# GPS.net
KiCad netlist of a schematic drawn in Altium Designer
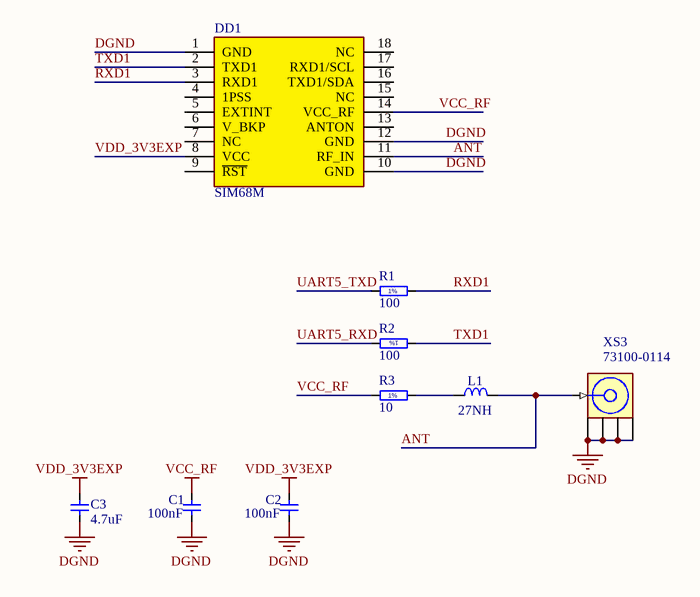
[diagram p0: GPS.SchDoc]

(export (version "E")
  (design (tool "Eeschema 10.0.6"))
  (components
    (comp (ref "C1")
      (value "100nF")
      (footprint "CAP0603R")
      (description "SMD 0805 Capacitor")
      (fields
        (field (name "PART NUMBER") "CC0603_100NF_50V_10%_X7R")
        (field (name "VOLTAGE") "50V")
        (field (name "AUTHOR") "I. Kuznetsov")
      )
      (libsource (lib "Capacitor") (part "CAP_NON_POLAR"))
    )
    (comp (ref "C2")
      (value "100nF")
      (footprint "CAP0603R")
      (description "SMD 0805 Capacitor")
      (fields
        (field (name "PART NUMBER") "CC0603_100NF_50V_10%_X7R")
        (field (name "VOLTAGE") "50V")
        (field (name "AUTHOR") "I. Kuznetsov")
      )
      (libsource (lib "Capacitor") (part "CAP_NON_POLAR"))
    )
    (comp (ref "C3")
      (value "4.7uF")
      (footprint "CAP0603R")
      (description "SMD 0805 Capacitor")
      (fields
        (field (name "PART NUMBER") "CC0603_4.7UF_6.3V_10%_X5R")
        (field (name "VOLTAGE") "6.3V")
        (field (name "AUTHOR") "I. Kuznetsov")
      )
      (libsource (lib "Capacitor") (part "CAP_NON_POLAR"))
    )
    (comp (ref "DD1")
      (value "SIM68M")
      (footprint "SIM68M")
      (fields (field (name "AUTHOR") "I. Kuznetsov"))
      (libsource (lib "IC And Semiconductor") (part "SIM68M"))
    )
    (comp (ref "L1")
      (value "27NH")
      (footprint "INDC1608X75N")
      (description "Inductor")
      (fields
        (field (name "PART NUMBER") "IND0603_TDK_MMZ1608B601C")
        (field (name "POWER") "500mA")
        (field (name "AUTHOR") "CERN DEM JMW")
      )
      (libsource (lib "Inductors & Transformers") (part "Inductor"))
    )
    (comp (ref "R1")
      (value "100")
      (footprint "RES0603R")
      (fields
        (field (name "PART NUMBER") "R0603_100R_1%_0.1W_100PPM")
        (field (name "POWER") "0.1W")
        (field (name "TOLERANCE") "±1%")
        (field (name "AUTHOR") "CERN DEM JLC")
      )
      (libsource (lib "Resistor") (part "Resistor - 1%"))
    )
    (comp (ref "R2")
      (value "100")
      (footprint "RES0603R")
      (fields
        (field (name "PART NUMBER") "R0603_100R_1%_0.1W_100PPM")
        (field (name "POWER") "0.1W")
        (field (name "TOLERANCE") "±1%")
        (field (name "AUTHOR") "CERN DEM JLC")
      )
      (libsource (lib "Resistor") (part "Resistor - 1%"))
    )
    (comp (ref "R3")
      (value "10")
      (footprint "RES0603R")
      (fields
        (field (name "PART NUMBER") "R0603_10R_1%_0.1W_200PPM")
        (field (name "POWER") "0.1W")
        (field (name "TOLERANCE") "±1%")
        (field (name "AUTHOR") "CERN DEM JLC")
      )
      (libsource (lib "Resistor") (part "Resistor - 1%"))
    )
    (comp (ref "XS3")
      (value "73100-0114")
      (footprint "73100-0114")
      (fields (field (name "MANUFACTURER") "MOLEX"))
      (libsource (lib "Connector") (part "COAX-F"))
    )
  )
  (nets
    (net (code "1") (name "/ANT") (class "Default")
      (node (ref "DD1") (pin "11") (pinfunction "RF_IN_11") (pintype "passive"))
      (node (ref "L1") (pin "2") (pinfunction "2_2") (pintype "passive"))
      (node (ref "XS3") (pin "1") (pinfunction "Signal_1") (pintype "input"))
    )
    (net (code "2") (name "/RXD1") (class "Default")
      (node (ref "DD1") (pin "3") (pinfunction "RXD1_3") (pintype "passive"))
      (node (ref "R1") (pin "2") (pinfunction "2_2") (pintype "passive"))
    )
    (net (code "3") (name "/TXD1") (class "Default")
      (node (ref "DD1") (pin "2") (pinfunction "TXD1_2") (pintype "passive"))
      (node (ref "R2") (pin "1") (pinfunction "1_1") (pintype "passive"))
    )
    (net (code "4") (name "/UART5_RXD") (class "Default")
      (node (ref "R2") (pin "2") (pinfunction "2_2") (pintype "passive"))
    )
    (net (code "5") (name "/UART5_TXD") (class "Default")
      (node (ref "R1") (pin "1") (pinfunction "1_1") (pintype "passive"))
    )
    (net (code "6") (name "DGND") (class "Default")
      (node (ref "C1") (pin "2") (pinfunction "2_2") (pintype "passive"))
      (node (ref "C2") (pin "2") (pinfunction "2_2") (pintype "passive"))
      (node (ref "C3") (pin "1") (pinfunction "1_1") (pintype "passive"))
      (node (ref "DD1") (pin "1") (pinfunction "GND_1") (pintype "passive"))
      (node (ref "DD1") (pin "10") (pinfunction "GND_10") (pintype "passive"))
      (node (ref "DD1") (pin "12") (pinfunction "GND_12") (pintype "passive"))
      (node (ref "XS3") (pin "2") (pinfunction "GND_2") (pintype "power_in"))
      (node (ref "XS3") (pin "3") (pinfunction "GND_3") (pintype "power_in"))
      (node (ref "XS3") (pin "4") (pinfunction "GND_4") (pintype "power_in"))
      (node (ref "XS3") (pin "5") (pinfunction "GND_5") (pintype "power_in"))
    )
    (net (code "7") (name "Net-(L1-Pad1)") (class "Default")
      (node (ref "L1") (pin "1") (pinfunction "1_1") (pintype "passive"))
      (node (ref "R3") (pin "2") (pinfunction "2_2") (pintype "passive"))
    )
    (net (code "8") (name "VCC_RF") (class "Default")
      (node (ref "C1") (pin "1") (pinfunction "1_1") (pintype "passive"))
      (node (ref "DD1") (pin "14") (pinfunction "VCC_RF_14") (pintype "passive"))
      (node (ref "R3") (pin "1") (pinfunction "1_1") (pintype "passive"))
    )
    (net (code "9") (name "VDD_3V3EXP") (class "Default")
      (node (ref "C2") (pin "1") (pinfunction "1_1") (pintype "passive"))
      (node (ref "C3") (pin "2") (pinfunction "2_2") (pintype "passive"))
      (node (ref "DD1") (pin "8") (pinfunction "VCC_8") (pintype "passive"))
    )
    (net (code "10") (name "unconnected-(DD1-1PSS-Pad4)") (class "Default")
      (node (ref "DD1") (pin "4") (pinfunction "1PSS_4") (pintype "passive"))
    )
    (net (code "11") (name "unconnected-(DD1-ANTON-Pad13)") (class "Default")
      (node (ref "DD1") (pin "13") (pinfunction "ANTON_13") (pintype "passive"))
    )
    (net (code "12") (name "unconnected-(DD1-EXTINT-Pad5)") (class "Default")
      (node (ref "DD1") (pin "5") (pinfunction "EXTINT_5") (pintype "passive"))
    )
    (net (code "13") (name "unconnected-(DD1-NC-Pad7)") (class "Default")
      (node (ref "DD1") (pin "7") (pinfunction "NC_7") (pintype "passive"))
    )
    (net (code "14") (name "unconnected-(DD1-NC-Pad15)") (class "Default")
      (node (ref "DD1") (pin "15") (pinfunction "NC_15") (pintype "passive"))
    )
    (net (code "15") (name "unconnected-(DD1-NC-Pad18)") (class "Default")
      (node (ref "DD1") (pin "18") (pinfunction "NC_18") (pintype "passive"))
    )
    (net (code "16") (name "unconnected-(DD1-RXD1{slash}SCL-Pad17)") (class "Default")
      (node (ref "DD1") (pin "17") (pinfunction "RXD1/SCL_17") (pintype "passive"))
    )
    (net (code "17") (name "unconnected-(DD1-TXD1{slash}SDA-Pad16)") (class "Default")
      (node (ref "DD1") (pin "16") (pinfunction "TXD1/SDA_16") (pintype "passive"))
    )
    (net (code "18") (name "unconnected-(DD1-V_BKP-Pad6)") (class "Default")
      (node (ref "DD1") (pin "6") (pinfunction "V_BKP_6") (pintype "passive"))
    )
    (net (code "19") (name "unconnected-(DD1-~{RST}-Pad9)") (class "Default")
      (node (ref "DD1") (pin "9") (pinfunction "~{RST}_9") (pintype "passive"))
    )
  )
)
